# 3ch_mix.net
KiCad netlist of a schematic drawn in EAGLE
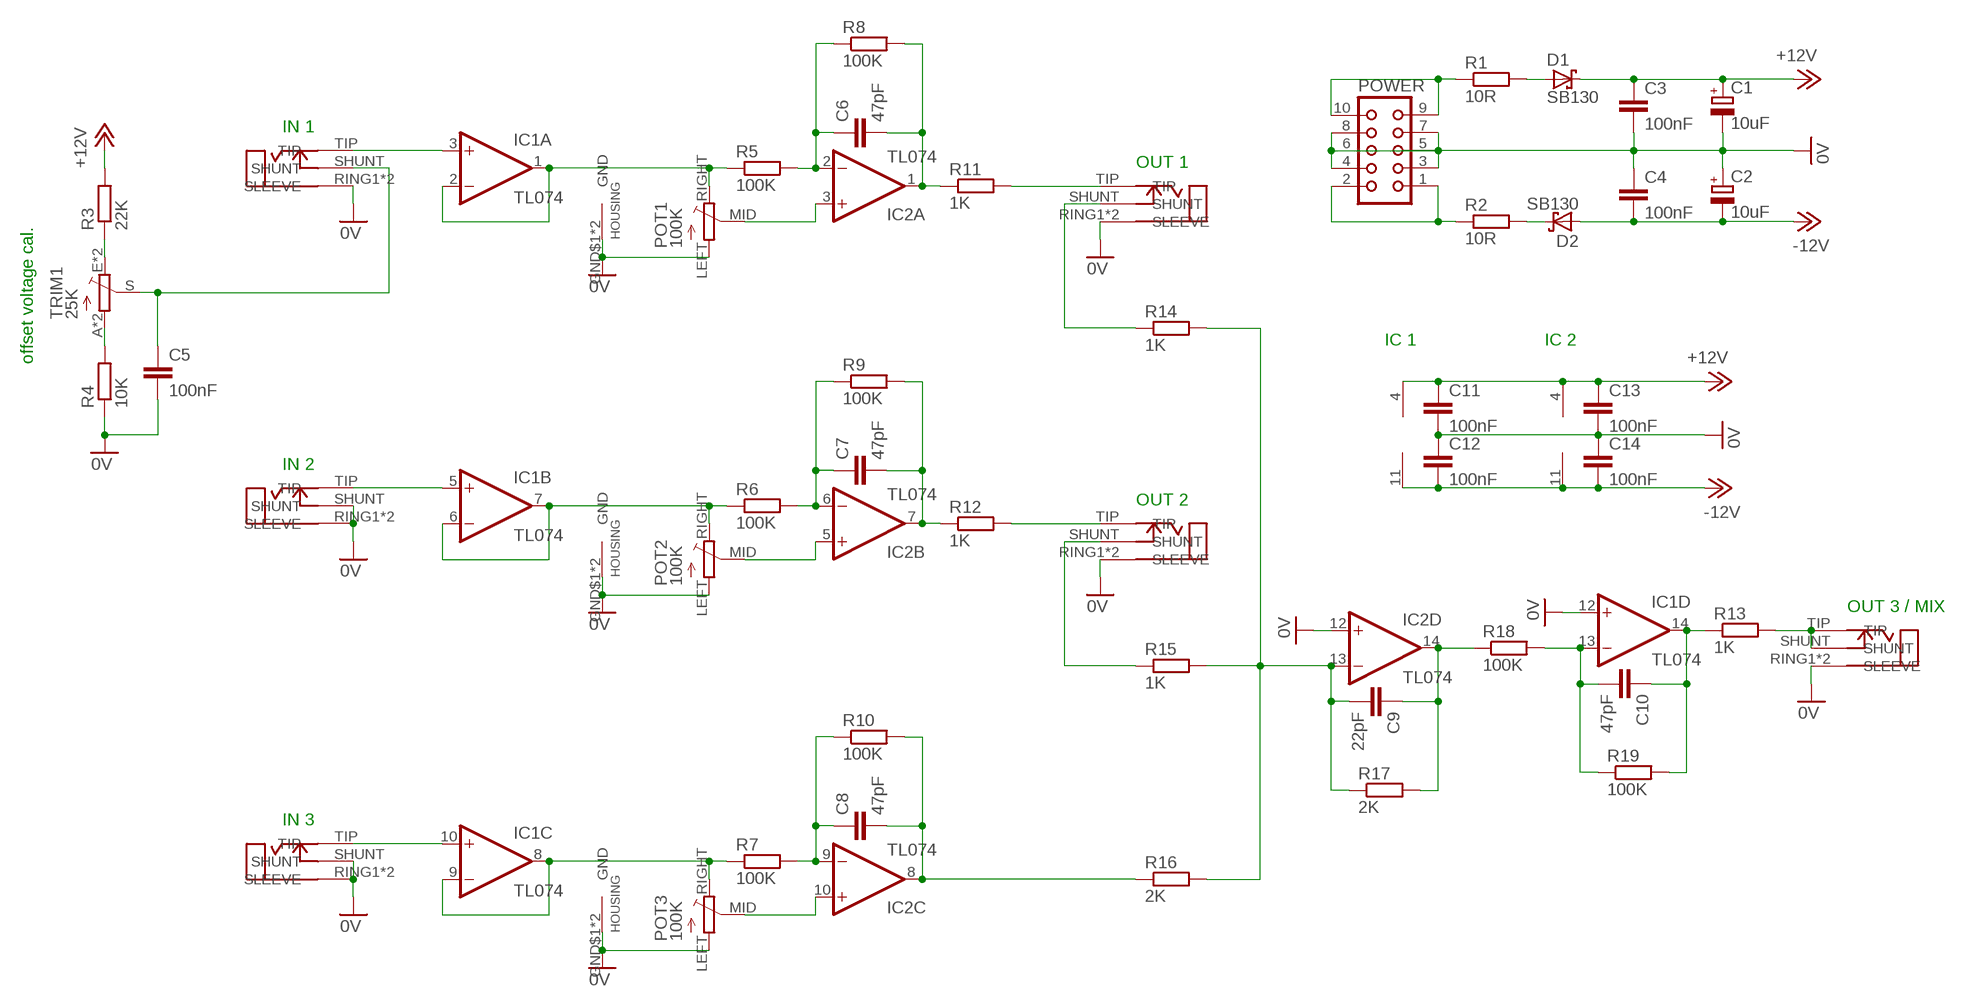
[diagram p0: schematic, sheet 1]

(export (version "E")
  (design (tool "Eeschema 10.0.6"))
  (components
    (comp (ref "C1")
      (value "10uF")
      (footprint "eagle-import:E2-5")
      (libsource (lib "eagle-import") (part "CPOL-EUE2-5"))
    )
    (comp (ref "C2")
      (value "10uF")
      (footprint "eagle-import:E2-5")
      (libsource (lib "eagle-import") (part "CPOL-EUE2-5"))
    )
    (comp (ref "C3")
      (value "100nF")
      (footprint "eagle-import:C025-024X044")
      (libsource (lib "eagle-import") (part "C-EU025-024X044"))
    )
    (comp (ref "C4")
      (value "100nF")
      (footprint "eagle-import:C025-024X044")
      (libsource (lib "eagle-import") (part "C-EU025-024X044"))
    )
    (comp (ref "C5")
      (value "100nF")
      (footprint "eagle-import:C025-024X044")
      (libsource (lib "eagle-import") (part "C-EU025-024X044"))
    )
    (comp (ref "C6")
      (value "47pF")
      (footprint "eagle-import:C025-024X044")
      (libsource (lib "eagle-import") (part "C-EU025-024X044"))
    )
    (comp (ref "C7")
      (value "47pF")
      (footprint "eagle-import:C025-024X044")
      (libsource (lib "eagle-import") (part "C-EU025-024X044"))
    )
    (comp (ref "C8")
      (value "47pF")
      (footprint "eagle-import:C025-024X044")
      (libsource (lib "eagle-import") (part "C-EU025-024X044"))
    )
    (comp (ref "C9")
      (value "22pF")
      (footprint "eagle-import:C025-024X044")
      (libsource (lib "eagle-import") (part "C-EU025-024X044"))
    )
    (comp (ref "C10")
      (value "47pF")
      (footprint "eagle-import:C025-024X044")
      (libsource (lib "eagle-import") (part "C-EU025-024X044"))
    )
    (comp (ref "C11")
      (value "100nF")
      (footprint "eagle-import:C025-024X044")
      (libsource (lib "eagle-import") (part "C-EU025-024X044"))
    )
    (comp (ref "C12")
      (value "100nF")
      (footprint "eagle-import:C025-024X044")
      (libsource (lib "eagle-import") (part "C-EU025-024X044"))
    )
    (comp (ref "C13")
      (value "100nF")
      (footprint "eagle-import:C025-024X044")
      (libsource (lib "eagle-import") (part "C-EU025-024X044"))
    )
    (comp (ref "C14")
      (value "100nF")
      (footprint "eagle-import:C025-024X044")
      (libsource (lib "eagle-import") (part "C-EU025-024X044"))
    )
    (comp (ref "D1")
      (value "SB130")
      (footprint "eagle-import:DO41-7")
      (libsource (lib "eagle-import") (part "SB130DO-204AL"))
    )
    (comp (ref "D2")
      (value "SB130")
      (footprint "eagle-import:DO41-7")
      (libsource (lib "eagle-import") (part "SB130DO-204AL"))
    )
    (comp (ref "IC1")
      (value "TL074")
      (footprint "eagle-import:DIL14")
      (libsource (lib "eagle-import") (part "TL074P"))
    )
    (comp (ref "IC2")
      (value "TL074")
      (footprint "eagle-import:DIL14")
      (libsource (lib "eagle-import") (part "TL074P"))
    )
    (comp (ref "IN1")
      (value "ERTHENVAR_3.5MM_JACK")
      (footprint "eagle-import:ERTHENVAR")
      (libsource (lib "eagle-import") (part "ERTHENVAR_3.5MM_JACK"))
    )
    (comp (ref "IN2")
      (value "ERTHENVAR_3.5MM_JACK")
      (footprint "eagle-import:ERTHENVAR")
      (libsource (lib "eagle-import") (part "ERTHENVAR_3.5MM_JACK"))
    )
    (comp (ref "IN3")
      (value "ERTHENVAR_3.5MM_JACK")
      (footprint "eagle-import:ERTHENVAR")
      (libsource (lib "eagle-import") (part "ERTHENVAR_3.5MM_JACK"))
    )
    (comp (ref "OUT1")
      (value "ERTHENVAR_3.5MM_JACK")
      (footprint "eagle-import:ERTHENVAR")
      (libsource (lib "eagle-import") (part "ERTHENVAR_3.5MM_JACK"))
    )
    (comp (ref "OUT2")
      (value "ERTHENVAR_3.5MM_JACK")
      (footprint "eagle-import:ERTHENVAR")
      (libsource (lib "eagle-import") (part "ERTHENVAR_3.5MM_JACK"))
    )
    (comp (ref "OUT3")
      (value "ERTHENVAR_3.5MM_JACK")
      (footprint "eagle-import:ERTHENVAR")
      (libsource (lib "eagle-import") (part "ERTHENVAR_3.5MM_JACK"))
    )
    (comp (ref "POT1")
      (value "100K")
      (footprint "eagle-import:POT-ALPHA9")
      (libsource (lib "eagle-import") (part "POT-ALPHA9"))
    )
    (comp (ref "POT2")
      (value "100K")
      (footprint "eagle-import:POT-ALPHA9")
      (libsource (lib "eagle-import") (part "POT-ALPHA9"))
    )
    (comp (ref "POT3")
      (value "100K")
      (footprint "eagle-import:POT-ALPHA9")
      (libsource (lib "eagle-import") (part "POT-ALPHA9"))
    )
    (comp (ref "POWER")
      (value "CON10L")
      (footprint "eagle-import:CON10L")
      (libsource (lib "eagle-import") (part "CON10L"))
    )
    (comp (ref "R1")
      (value "10R")
      (footprint "eagle-import:0207_9")
      (libsource (lib "eagle-import") (part "R-EU_0207/10"))
    )
    (comp (ref "R2")
      (value "10R")
      (footprint "eagle-import:0207_9")
      (libsource (lib "eagle-import") (part "R-EU_0207/10"))
    )
    (comp (ref "R3")
      (value "22K")
      (footprint "eagle-import:0207_9")
      (libsource (lib "eagle-import") (part "R-EU_0207/10"))
    )
    (comp (ref "R4")
      (value "10K")
      (footprint "eagle-import:0207_9")
      (libsource (lib "eagle-import") (part "R-EU_0207/10"))
    )
    (comp (ref "R5")
      (value "100K")
      (footprint "eagle-import:0207_9")
      (libsource (lib "eagle-import") (part "R-EU_0207/10"))
    )
    (comp (ref "R6")
      (value "100K")
      (footprint "eagle-import:0207_9")
      (libsource (lib "eagle-import") (part "R-EU_0207/10"))
    )
    (comp (ref "R7")
      (value "100K")
      (footprint "eagle-import:0207_9")
      (libsource (lib "eagle-import") (part "R-EU_0207/10"))
    )
    (comp (ref "R8")
      (value "100K")
      (footprint "eagle-import:0207_9")
      (libsource (lib "eagle-import") (part "R-EU_0207/10"))
    )
    (comp (ref "R9")
      (value "100K")
      (footprint "eagle-import:0207_9")
      (libsource (lib "eagle-import") (part "R-EU_0207/10"))
    )
    (comp (ref "R10")
      (value "100K")
      (footprint "eagle-import:0207_9")
      (libsource (lib "eagle-import") (part "R-EU_0207/10"))
    )
    (comp (ref "R11")
      (value "1K")
      (footprint "eagle-import:0207_9")
      (libsource (lib "eagle-import") (part "R-EU_0207/10"))
    )
    (comp (ref "R12")
      (value "1K")
      (footprint "eagle-import:0207_9")
      (libsource (lib "eagle-import") (part "R-EU_0207/10"))
    )
    (comp (ref "R13")
      (value "1K")
      (footprint "eagle-import:0207_9")
      (libsource (lib "eagle-import") (part "R-EU_0207/10"))
    )
    (comp (ref "R14")
      (value "1K")
      (footprint "eagle-import:0207_9")
      (libsource (lib "eagle-import") (part "R-EU_0207/10"))
    )
    (comp (ref "R15")
      (value "1K")
      (footprint "eagle-import:0207_9")
      (libsource (lib "eagle-import") (part "R-EU_0207/10"))
    )
    (comp (ref "R16")
      (value "2K")
      (footprint "eagle-import:0207_9")
      (libsource (lib "eagle-import") (part "R-EU_0207/10"))
    )
    (comp (ref "R17")
      (value "2K")
      (footprint "eagle-import:0207_9")
      (libsource (lib "eagle-import") (part "R-EU_0207/10"))
    )
    (comp (ref "R18")
      (value "100K")
      (footprint "eagle-import:0207_9")
      (libsource (lib "eagle-import") (part "R-EU_0207/10"))
    )
    (comp (ref "R19")
      (value "100K")
      (footprint "eagle-import:0207_9")
      (libsource (lib "eagle-import") (part "R-EU_0207/10"))
    )
    (comp (ref "TRIM1")
      (value "25K")
      (footprint "eagle-import:B25P")
      (libsource (lib "eagle-import") (part "TRIM_EU-B25P"))
    )
  )
  (nets
    (net (code "1") (name "+12V") (class "Default")
      (node (ref "C1") (pin "+") (pinfunction "+_+") (pintype "passive"))
      (node (ref "C11") (pin "1") (pinfunction "1_1") (pintype "passive"))
      (node (ref "C13") (pin "1") (pinfunction "1_1") (pintype "passive"))
      (node (ref "C3") (pin "1") (pinfunction "1_1") (pintype "passive"))
      (node (ref "D1") (pin "C") (pinfunction "C_C") (pintype "passive"))
      (node (ref "IC1") (pin "4") (pinfunction "V+_4") (pintype "power_in"))
      (node (ref "IC2") (pin "4") (pinfunction "V+_4") (pintype "power_in"))
      (node (ref "R3") (pin "2") (pinfunction "2_2") (pintype "passive"))
    )
    (net (code "2") (name "-12V") (class "Default")
      (node (ref "C12") (pin "2") (pinfunction "2_2") (pintype "passive"))
      (node (ref "C14") (pin "2") (pinfunction "2_2") (pintype "passive"))
      (node (ref "C2") (pin "-") (pinfunction "-_-") (pintype "passive"))
      (node (ref "C4") (pin "2") (pinfunction "2_2") (pintype "passive"))
      (node (ref "D2") (pin "A") (pinfunction "A_A") (pintype "passive"))
      (node (ref "IC1") (pin "11") (pinfunction "V-_11") (pintype "power_in"))
      (node (ref "IC2") (pin "11") (pinfunction "V-_11") (pintype "power_in"))
    )
    (net (code "3") (name "0V") (class "Default")
      (node (ref "C1") (pin "-") (pinfunction "-_-") (pintype "passive"))
      (node (ref "C11") (pin "2") (pinfunction "2_2") (pintype "passive"))
      (node (ref "C12") (pin "1") (pinfunction "1_1") (pintype "passive"))
      (node (ref "C13") (pin "2") (pinfunction "2_2") (pintype "passive"))
      (node (ref "C14") (pin "1") (pinfunction "1_1") (pintype "passive"))
      (node (ref "C2") (pin "+") (pinfunction "+_+") (pintype "passive"))
      (node (ref "C3") (pin "2") (pinfunction "2_2") (pintype "passive"))
      (node (ref "C4") (pin "1") (pinfunction "1_1") (pintype "passive"))
      (node (ref "C5") (pin "2") (pinfunction "2_2") (pintype "passive"))
      (node (ref "IC1") (pin "12") (pinfunction "+IN_12") (pintype "input"))
      (node (ref "IC2") (pin "12") (pinfunction "+IN_12") (pintype "input"))
      (node (ref "IN1") (pin "RING1") (pinfunction "SLEEVE_RING1") (pintype "bidirectional"))
      (node (ref "IN1") (pin "RING2") (pinfunction "SLEEVE_RING2") (pintype "bidirectional"))
      (node (ref "IN2") (pin "RING1") (pinfunction "SLEEVE_RING1") (pintype "bidirectional"))
      (node (ref "IN2") (pin "RING2") (pinfunction "SLEEVE_RING2") (pintype "bidirectional"))
      (node (ref "IN2") (pin "SHUNT") (pinfunction "SHUNT_SHUNT") (pintype "bidirectional"))
      (node (ref "IN3") (pin "RING1") (pinfunction "SLEEVE_RING1") (pintype "bidirectional"))
      (node (ref "IN3") (pin "RING2") (pinfunction "SLEEVE_RING2") (pintype "bidirectional"))
      (node (ref "IN3") (pin "SHUNT") (pinfunction "SHUNT_SHUNT") (pintype "bidirectional"))
      (node (ref "OUT1") (pin "RING1") (pinfunction "SLEEVE_RING1") (pintype "bidirectional"))
      (node (ref "OUT1") (pin "RING2") (pinfunction "SLEEVE_RING2") (pintype "bidirectional"))
      (node (ref "OUT2") (pin "RING1") (pinfunction "SLEEVE_RING1") (pintype "bidirectional"))
      (node (ref "OUT2") (pin "RING2") (pinfunction "SLEEVE_RING2") (pintype "bidirectional"))
      (node (ref "OUT3") (pin "RING1") (pinfunction "SLEEVE_RING1") (pintype "bidirectional"))
      (node (ref "OUT3") (pin "RING2") (pinfunction "SLEEVE_RING2") (pintype "bidirectional"))
      (node (ref "POT1") (pin "GND$1") (pinfunction "GND_GND$1") (pintype "bidirectional"))
      (node (ref "POT1") (pin "GND$2") (pinfunction "GND_GND$2") (pintype "bidirectional"))
      (node (ref "POT1") (pin "LEFT") (pinfunction "LEFT_LEFT") (pintype "passive"))
      (node (ref "POT2") (pin "GND$1") (pinfunction "GND_GND$1") (pintype "bidirectional"))
      (node (ref "POT2") (pin "GND$2") (pinfunction "GND_GND$2") (pintype "bidirectional"))
      (node (ref "POT2") (pin "LEFT") (pinfunction "LEFT_LEFT") (pintype "passive"))
      (node (ref "POT3") (pin "GND$1") (pinfunction "GND_GND$1") (pintype "bidirectional"))
      (node (ref "POT3") (pin "GND$2") (pinfunction "GND_GND$2") (pintype "bidirectional"))
      (node (ref "POT3") (pin "LEFT") (pinfunction "LEFT_LEFT") (pintype "passive"))
      (node (ref "POWER") (pin "3") (pinfunction "3_3") (pintype "passive"))
      (node (ref "POWER") (pin "4") (pinfunction "4_4") (pintype "passive"))
      (node (ref "POWER") (pin "5") (pinfunction "5_5") (pintype "passive"))
      (node (ref "POWER") (pin "6") (pinfunction "6_6") (pintype "passive"))
      (node (ref "POWER") (pin "7") (pinfunction "7_7") (pintype "passive"))
      (node (ref "POWER") (pin "8") (pinfunction "8_8") (pintype "passive"))
      (node (ref "R4") (pin "1") (pinfunction "1_1") (pintype "passive"))
    )
    (net (code "4") (name "Net-(C5-Pad1)") (class "Default")
      (node (ref "C5") (pin "1") (pinfunction "1_1") (pintype "passive"))
      (node (ref "IN1") (pin "SHUNT") (pinfunction "SHUNT_SHUNT") (pintype "bidirectional"))
      (node (ref "TRIM1") (pin "S") (pinfunction "S_S") (pintype "passive"))
    )
    (net (code "5") (name "Net-(D1-PadA)") (class "Default")
      (node (ref "D1") (pin "A") (pinfunction "A_A") (pintype "passive"))
      (node (ref "R1") (pin "2") (pinfunction "2_2") (pintype "passive"))
    )
    (net (code "6") (name "Net-(D2-PadC)") (class "Default")
      (node (ref "D2") (pin "C") (pinfunction "C_C") (pintype "passive"))
      (node (ref "R2") (pin "2") (pinfunction "2_2") (pintype "passive"))
    )
    (net (code "7") (name "Net-(IC1A-+IN)") (class "Default")
      (node (ref "IC1") (pin "3") (pinfunction "+IN_3") (pintype "input"))
      (node (ref "IN1") (pin "TIP") (pinfunction "TIP_TIP") (pintype "bidirectional"))
    )
    (net (code "8") (name "Net-(IC1A--IN)") (class "Default")
      (node (ref "IC1") (pin "1") (pinfunction "OUT_1") (pintype "output"))
      (node (ref "IC1") (pin "2") (pinfunction "-IN_2") (pintype "input"))
      (node (ref "POT1") (pin "RIGHT") (pinfunction "RIGHT_RIGHT") (pintype "passive"))
      (node (ref "R5") (pin "1") (pinfunction "1_1") (pintype "passive"))
    )
    (net (code "9") (name "Net-(IC1B-+IN)") (class "Default")
      (node (ref "IC1") (pin "5") (pinfunction "+IN_5") (pintype "input"))
      (node (ref "IN2") (pin "TIP") (pinfunction "TIP_TIP") (pintype "bidirectional"))
    )
    (net (code "10") (name "Net-(IC1B--IN)") (class "Default")
      (node (ref "IC1") (pin "6") (pinfunction "-IN_6") (pintype "input"))
      (node (ref "IC1") (pin "7") (pinfunction "OUT_7") (pintype "output"))
      (node (ref "POT2") (pin "RIGHT") (pinfunction "RIGHT_RIGHT") (pintype "passive"))
      (node (ref "R6") (pin "1") (pinfunction "1_1") (pintype "passive"))
    )
    (net (code "11") (name "Net-(IC1C-+IN)") (class "Default")
      (node (ref "IC1") (pin "10") (pinfunction "+IN_10") (pintype "input"))
      (node (ref "IN3") (pin "TIP") (pinfunction "TIP_TIP") (pintype "bidirectional"))
    )
    (net (code "12") (name "Net-(IC1C--IN)") (class "Default")
      (node (ref "IC1") (pin "8") (pinfunction "OUT_8") (pintype "output"))
      (node (ref "IC1") (pin "9") (pinfunction "-IN_9") (pintype "input"))
      (node (ref "POT3") (pin "RIGHT") (pinfunction "RIGHT_RIGHT") (pintype "passive"))
      (node (ref "R7") (pin "1") (pinfunction "1_1") (pintype "passive"))
    )
    (net (code "13") (name "Net-(IC1D--IN)") (class "Default")
      (node (ref "C10") (pin "2") (pinfunction "2_2") (pintype "passive"))
      (node (ref "IC1") (pin "13") (pinfunction "-IN_13") (pintype "input"))
      (node (ref "R18") (pin "2") (pinfunction "2_2") (pintype "passive"))
      (node (ref "R19") (pin "1") (pinfunction "1_1") (pintype "passive"))
    )
    (net (code "14") (name "Net-(IC1D-OUT)") (class "Default")
      (node (ref "C10") (pin "1") (pinfunction "1_1") (pintype "passive"))
      (node (ref "IC1") (pin "14") (pinfunction "OUT_14") (pintype "output"))
      (node (ref "R13") (pin "1") (pinfunction "1_1") (pintype "passive"))
      (node (ref "R19") (pin "2") (pinfunction "2_2") (pintype "passive"))
    )
    (net (code "15") (name "Net-(IC2A-+IN)") (class "Default")
      (node (ref "IC2") (pin "3") (pinfunction "+IN_3") (pintype "input"))
      (node (ref "POT1") (pin "MID") (pinfunction "MID_MID") (pintype "passive"))
    )
    (net (code "16") (name "Net-(IC2A--IN)") (class "Default")
      (node (ref "C6") (pin "1") (pinfunction "1_1") (pintype "passive"))
      (node (ref "IC2") (pin "2") (pinfunction "-IN_2") (pintype "input"))
      (node (ref "R5") (pin "2") (pinfunction "2_2") (pintype "passive"))
      (node (ref "R8") (pin "1") (pinfunction "1_1") (pintype "passive"))
    )
    (net (code "17") (name "Net-(IC2A-OUT)") (class "Default")
      (node (ref "C6") (pin "2") (pinfunction "2_2") (pintype "passive"))
      (node (ref "IC2") (pin "1") (pinfunction "OUT_1") (pintype "output"))
      (node (ref "R11") (pin "1") (pinfunction "1_1") (pintype "passive"))
      (node (ref "R8") (pin "2") (pinfunction "2_2") (pintype "passive"))
    )
    (net (code "18") (name "Net-(IC2B-+IN)") (class "Default")
      (node (ref "IC2") (pin "5") (pinfunction "+IN_5") (pintype "input"))
      (node (ref "POT2") (pin "MID") (pinfunction "MID_MID") (pintype "passive"))
    )
    (net (code "19") (name "Net-(IC2B--IN)") (class "Default")
      (node (ref "C7") (pin "1") (pinfunction "1_1") (pintype "passive"))
      (node (ref "IC2") (pin "6") (pinfunction "-IN_6") (pintype "input"))
      (node (ref "R6") (pin "2") (pinfunction "2_2") (pintype "passive"))
      (node (ref "R9") (pin "1") (pinfunction "1_1") (pintype "passive"))
    )
    (net (code "20") (name "Net-(IC2B-OUT)") (class "Default")
      (node (ref "C7") (pin "2") (pinfunction "2_2") (pintype "passive"))
      (node (ref "IC2") (pin "7") (pinfunction "OUT_7") (pintype "output"))
      (node (ref "R12") (pin "1") (pinfunction "1_1") (pintype "passive"))
      (node (ref "R9") (pin "2") (pinfunction "2_2") (pintype "passive"))
    )
    (net (code "21") (name "Net-(IC2C-+IN)") (class "Default")
      (node (ref "IC2") (pin "10") (pinfunction "+IN_10") (pintype "input"))
      (node (ref "POT3") (pin "MID") (pinfunction "MID_MID") (pintype "passive"))
    )
    (net (code "22") (name "Net-(IC2C--IN)") (class "Default")
      (node (ref "C8") (pin "1") (pinfunction "1_1") (pintype "passive"))
      (node (ref "IC2") (pin "9") (pinfunction "-IN_9") (pintype "input"))
      (node (ref "R10") (pin "1") (pinfunction "1_1") (pintype "passive"))
      (node (ref "R7") (pin "2") (pinfunction "2_2") (pintype "passive"))
    )
    (net (code "23") (name "Net-(IC2C-OUT)") (class "Default")
      (node (ref "C8") (pin "2") (pinfunction "2_2") (pintype "passive"))
      (node (ref "IC2") (pin "8") (pinfunction "OUT_8") (pintype "output"))
      (node (ref "R10") (pin "2") (pinfunction "2_2") (pintype "passive"))
      (node (ref "R16") (pin "1") (pinfunction "1_1") (pintype "passive"))
    )
    (net (code "24") (name "Net-(IC2D--IN)") (class "Default")
      (node (ref "C9") (pin "2") (pinfunction "2_2") (pintype "passive"))
      (node (ref "IC2") (pin "13") (pinfunction "-IN_13") (pintype "input"))
      (node (ref "R14") (pin "2") (pinfunction "2_2") (pintype "passive"))
      (node (ref "R15") (pin "2") (pinfunction "2_2") (pintype "passive"))
      (node (ref "R16") (pin "2") (pinfunction "2_2") (pintype "passive"))
      (node (ref "R17") (pin "1") (pinfunction "1_1") (pintype "passive"))
    )
    (net (code "25") (name "Net-(IC2D-OUT)") (class "Default")
      (node (ref "C9") (pin "1") (pinfunction "1_1") (pintype "passive"))
      (node (ref "IC2") (pin "14") (pinfunction "OUT_14") (pintype "output"))
      (node (ref "R17") (pin "2") (pinfunction "2_2") (pintype "passive"))
      (node (ref "R18") (pin "1") (pinfunction "1_1") (pintype "passive"))
    )
    (net (code "26") (name "Net-(OUT1-PadSHUNT)") (class "Default")
      (node (ref "OUT1") (pin "SHUNT") (pinfunction "SHUNT_SHUNT") (pintype "bidirectional"))
      (node (ref "R14") (pin "1") (pinfunction "1_1") (pintype "passive"))
    )
    (net (code "27") (name "Net-(OUT1-PadTIP)") (class "Default")
      (node (ref "OUT1") (pin "TIP") (pinfunction "TIP_TIP") (pintype "bidirectional"))
      (node (ref "R11") (pin "2") (pinfunction "2_2") (pintype "passive"))
    )
    (net (code "28") (name "Net-(OUT2-PadSHUNT)") (class "Default")
      (node (ref "OUT2") (pin "SHUNT") (pinfunction "SHUNT_SHUNT") (pintype "bidirectional"))
      (node (ref "R15") (pin "1") (pinfunction "1_1") (pintype "passive"))
    )
    (net (code "29") (name "Net-(OUT2-PadTIP)") (class "Default")
      (node (ref "OUT2") (pin "TIP") (pinfunction "TIP_TIP") (pintype "bidirectional"))
      (node (ref "R12") (pin "2") (pinfunction "2_2") (pintype "passive"))
    )
    (net (code "30") (name "Net-(OUT3-PadSHUNT)") (class "Default")
      (node (ref "OUT3") (pin "SHUNT") (pinfunction "SHUNT_SHUNT") (pintype "bidirectional"))
      (node (ref "OUT3") (pin "TIP") (pinfunction "TIP_TIP") (pintype "bidirectional"))
      (node (ref "R13") (pin "2") (pinfunction "2_2") (pintype "passive"))
    )
    (net (code "31") (name "Net-(POWER-Pad1)") (class "Default")
      (node (ref "POWER") (pin "1") (pinfunction "1_1") (pintype "passive"))
      (node (ref "POWER") (pin "2") (pinfunction "2_2") (pintype "passive"))
      (node (ref "R2") (pin "1") (pinfunction "1_1") (pintype "passive"))
    )
    (net (code "32") (name "Net-(POWER-Pad10)") (class "Default")
      (node (ref "POWER") (pin "10") (pinfunction "10_10") (pintype "passive"))
      (node (ref "POWER") (pin "9") (pinfunction "9_9") (pintype "passive"))
      (node (ref "R1") (pin "1") (pinfunction "1_1") (pintype "passive"))
    )
    (net (code "33") (name "Net-(R3-Pad1)") (class "Default")
      (node (ref "R3") (pin "1") (pinfunction "1_1") (pintype "passive"))
      (node (ref "TRIM1") (pin "E") (pinfunction "E_E") (pintype "passive"))
      (node (ref "TRIM1") (pin "EE") (pinfunction "E_EE") (pintype "passive"))
    )
    (net (code "34") (name "Net-(R4-Pad2)") (class "Default")
      (node (ref "R4") (pin "2") (pinfunction "2_2") (pintype "passive"))
      (node (ref "TRIM1") (pin "A") (pinfunction "A_A") (pintype "passive"))
      (node (ref "TRIM1") (pin "AA") (pinfunction "A_AA") (pintype "passive"))
    )
  )
)
